# Main.net
KiCad netlist of a schematic drawn in Altium Designer
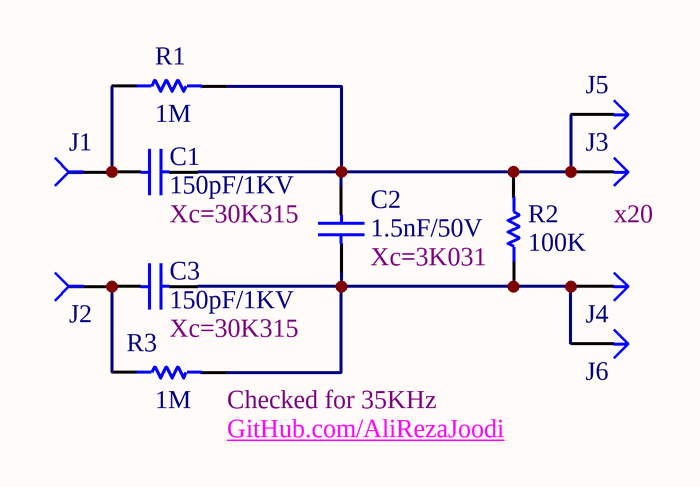
[diagram p0: Main.SchDoc]

(export (version "E")
  (design (tool "Eeschema 10.0.6"))
  (components
    (comp (ref "C1")
      (value "150pF/1KV")
      (footprint "THD_P15/L18/W4")
      (description "Capacitor, MKT")
      (libsource (lib "General") (part "Capacitor_Ceramic"))
    )
    (comp (ref "C2")
      (value "1.5nF/50V")
      (footprint "THD_P7.6/L10/W5.5/H9")
      (description "Capacitor, Polyester")
      (libsource (lib "General") (part "Capacitor_Ceramic"))
    )
    (comp (ref "C3")
      (value "150pF/1KV")
      (footprint "THD_P15/L18/W4")
      (description "Capacitor, MKT")
      (libsource (lib "General") (part "Capacitor_Ceramic"))
    )
    (comp (ref "J1")
      (value "Connector_Socket_1Pin_Female_2Form")
      (footprint "THD_C_BLK3")
      (description "Connector, Socket, 1Pin")
      (libsource (lib "Connector") (part "Connector_Socket_1Pin_Female_2Form"))
    )
    (comp (ref "J2")
      (value "Connector_Socket_1Pin_Female_2Form")
      (footprint "THD_C_BLK3")
      (description "Connector, Socket, 1Pin")
      (libsource (lib "Connector") (part "Connector_Socket_1Pin_Female_2Form"))
    )
    (comp (ref "J3")
      (value "Connector_Socket_1Pin_Male_2Form")
      (footprint "THD_C_BLK2")
      (description "Connector, Socket, 1Pin")
      (libsource (lib "Connector") (part "Connector_Socket_1Pin_Male_2Form"))
    )
    (comp (ref "J4")
      (value "Connector_Socket_1Pin_Male_2Form")
      (footprint "THD_C_BLK2")
      (description "Connector, Socket, 1Pin")
      (libsource (lib "Connector") (part "Connector_Socket_1Pin_Male_2Form"))
    )
    (comp (ref "J5")
      (value "Connector_Socket_1Pin_Male_2Form")
      (footprint "THD_C_BLK2")
      (description "Connector, Socket, 1Pin")
      (libsource (lib "Connector") (part "Connector_Socket_1Pin_Male_2Form"))
    )
    (comp (ref "J6")
      (value "Connector_Socket_1Pin_Male_2Form")
      (footprint "THD_C_BLK2")
      (description "Connector, Socket, 1Pin")
      (libsource (lib "Connector") (part "Connector_Socket_1Pin_Male_2Form"))
    )
    (comp (ref "R1")
      (value "1M")
      (footprint "THD_AXIAL0.4")
      (description "Resistor, 1/4W, 5%")
      (libsource (lib "General") (part "Resistor_2Form"))
    )
    (comp (ref "R2")
      (value "100K")
      (footprint "THD_AXIAL0.4")
      (description "Resistor, 1/4W, 5%")
      (libsource (lib "General") (part "Resistor_2Form"))
    )
    (comp (ref "R3")
      (value "1M")
      (footprint "THD_AXIAL0.4")
      (description "Resistor, 1/4W, 5%")
      (libsource (lib "General") (part "Resistor_2Form"))
    )
  )
  (nets
    (net (code "1") (name "Net-(J1-A)") (class "Default")
      (node (ref "C1") (pin "2") (pinfunction "2_2") (pintype "passive"))
      (node (ref "J1") (pin "1") (pinfunction "A_1") (pintype "passive"))
      (node (ref "R1") (pin "2") (pinfunction "2_2") (pintype "passive"))
    )
    (net (code "2") (name "Net-(J2-A)") (class "Default")
      (node (ref "C3") (pin "2") (pinfunction "2_2") (pintype "passive"))
      (node (ref "J2") (pin "1") (pinfunction "A_1") (pintype "passive"))
      (node (ref "R3") (pin "2") (pinfunction "2_2") (pintype "passive"))
    )
    (net (code "3") (name "Net-(J3-A)") (class "Default")
      (node (ref "C1") (pin "1") (pinfunction "1_1") (pintype "passive"))
      (node (ref "C2") (pin "2") (pinfunction "2_2") (pintype "passive"))
      (node (ref "J3") (pin "1") (pinfunction "A_1") (pintype "passive"))
      (node (ref "J5") (pin "1") (pinfunction "A_1") (pintype "passive"))
      (node (ref "R1") (pin "1") (pinfunction "1_1") (pintype "passive"))
      (node (ref "R2") (pin "1") (pinfunction "1_1") (pintype "passive"))
    )
    (net (code "4") (name "Net-(J4-A)") (class "Default")
      (node (ref "C2") (pin "1") (pinfunction "1_1") (pintype "passive"))
      (node (ref "C3") (pin "1") (pinfunction "1_1") (pintype "passive"))
      (node (ref "J4") (pin "1") (pinfunction "A_1") (pintype "passive"))
      (node (ref "J6") (pin "1") (pinfunction "A_1") (pintype "passive"))
      (node (ref "R2") (pin "2") (pinfunction "2_2") (pintype "passive"))
      (node (ref "R3") (pin "1") (pinfunction "1_1") (pintype "passive"))
    )
  )
)
